# microusb_li_ion_charger.net
KiCad netlist of a schematic drawn in EAGLE
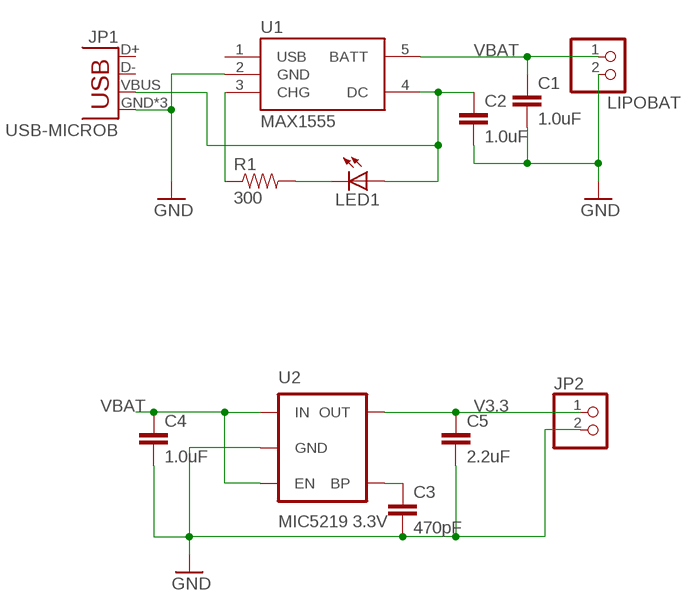
[diagram p0: schematic, sheet 1]

(export (version "E")
  (design (tool "Eeschema 10.0.6"))
  (components
    (comp (ref "C1")
      (value "1.0uF")
      (footprint "eagle-import:0805")
      (libsource (lib "eagle-import") (part "1.0UF-25V-+80/-20(0805)"))
    )
    (comp (ref "C2")
      (value "1.0uF")
      (footprint "eagle-import:0805")
      (libsource (lib "eagle-import") (part "1.0UF-25V-+80/-20(0805)"))
    )
    (comp (ref "C3")
      (value "470pF")
      (footprint "eagle-import:0805")
      (libsource (lib "eagle-import") (part "1.0UF-25V-+80/-20(0805)"))
    )
    (comp (ref "C4")
      (value "1.0uF")
      (footprint "eagle-import:0805")
      (libsource (lib "eagle-import") (part "1.0UF-25V-+80/-20(0805)"))
    )
    (comp (ref "C5")
      (value "2.2uF")
      (footprint "eagle-import:0805")
      (libsource (lib "eagle-import") (part "1.0UF-25V-+80/-20(0805)"))
    )
    (comp (ref "JP1")
      (value "USB-MICROB")
      (footprint "eagle-import:USB-MICROB")
      (libsource (lib "eagle-import") (part "USB-MICROB"))
    )
    (comp (ref "JP2")
      (value "PINHD-1X2")
      (footprint "eagle-import:1X02")
      (libsource (lib "eagle-import") (part "PINHD-1X2"))
    )
    (comp (ref "LED1")
      (value "LEDCHIP-LED0805")
      (footprint "eagle-import:CHIP-LED0805")
      (libsource (lib "eagle-import") (part "LEDCHIP-LED0805"))
    )
    (comp (ref "LIPOBAT")
      (value "JST_2PIN-SMT")
      (footprint "eagle-import:JST-PH-2-SMT")
      (libsource (lib "eagle-import") (part "JST_2PIN-SMT"))
    )
    (comp (ref "R1")
      (value "300")
      (footprint "eagle-import:0805")
      (libsource (lib "eagle-import") (part "RESISTOR0805-RES"))
    )
    (comp (ref "U1")
      (value "MAX1555")
      (footprint "eagle-import:SOT23-5")
      (libsource (lib "eagle-import") (part "MAX1555"))
    )
    (comp (ref "U2")
      (value "MIC5219 3.3V")
      (footprint "eagle-import:SOT23-5")
      (libsource (lib "eagle-import") (part "V_REG_MIC52193.3V"))
    )
  )
  (nets
    (net (code "1") (name "/V3.3") (class "Default")
      (node (ref "C5") (pin "1") (pinfunction "1_1") (pintype "passive"))
      (node (ref "JP2") (pin "1") (pinfunction "1_1") (pintype "passive"))
      (node (ref "U2") (pin "5") (pinfunction "OUT_5") (pintype "passive"))
    )
    (net (code "2") (name "/VBAT") (class "Default")
      (node (ref "C1") (pin "1") (pinfunction "1_1") (pintype "passive"))
      (node (ref "C4") (pin "1") (pinfunction "1_1") (pintype "passive"))
      (node (ref "LIPOBAT") (pin "1") (pinfunction "2_1") (pintype "passive"))
      (node (ref "U1") (pin "5") (pinfunction "BATT_5") (pintype "bidirectional"))
      (node (ref "U2") (pin "1") (pinfunction "IN_1") (pintype "input"))
      (node (ref "U2") (pin "3") (pinfunction "EN_3") (pintype "input"))
    )
    (net (code "3") (name "GND") (class "Default")
      (node (ref "C1") (pin "2") (pinfunction "2_2") (pintype "passive"))
      (node (ref "C2") (pin "2") (pinfunction "2_2") (pintype "passive"))
      (node (ref "C3") (pin "2") (pinfunction "2_2") (pintype "passive"))
      (node (ref "C4") (pin "2") (pinfunction "2_2") (pintype "passive"))
      (node (ref "C5") (pin "2") (pinfunction "2_2") (pintype "passive"))
      (node (ref "JP1") (pin "GND") (pinfunction "GND_GND") (pintype "bidirectional"))
      (node (ref "JP1") (pin "MT1") (pinfunction "GND_MT1") (pintype "bidirectional"))
      (node (ref "JP1") (pin "MT2") (pinfunction "GND_MT2") (pintype "bidirectional"))
      (node (ref "JP2") (pin "2") (pinfunction "2_2") (pintype "passive"))
      (node (ref "LIPOBAT") (pin "2") (pinfunction "1_2") (pintype "passive"))
      (node (ref "U1") (pin "2") (pinfunction "GND_2") (pintype "bidirectional"))
      (node (ref "U2") (pin "2") (pinfunction "GND_2") (pintype "input"))
    )
    (net (code "4") (name "Net-(LED1-PadC)") (class "Default")
      (node (ref "LED1") (pin "C") (pinfunction "C_C") (pintype "passive"))
      (node (ref "R1") (pin "2") (pinfunction "2_2") (pintype "passive"))
    )
    (net (code "5") (name "Net-(U1-CHG)") (class "Default")
      (node (ref "R1") (pin "1") (pinfunction "1_1") (pintype "passive"))
      (node (ref "U1") (pin "3") (pinfunction "CHG_3") (pintype "bidirectional"))
    )
    (net (code "6") (name "Net-(U1-DC)") (class "Default")
      (node (ref "C2") (pin "1") (pinfunction "1_1") (pintype "passive"))
      (node (ref "JP1") (pin "VBUS") (pinfunction "VBUS_VBUS") (pintype "bidirectional"))
      (node (ref "LED1") (pin "A") (pinfunction "A_A") (pintype "passive"))
      (node (ref "U1") (pin "4") (pinfunction "DC_4") (pintype "bidirectional"))
    )
    (net (code "7") (name "Net-(U2-BP)") (class "Default")
      (node (ref "C3") (pin "1") (pinfunction "1_1") (pintype "passive"))
      (node (ref "U2") (pin "4") (pinfunction "BP_4") (pintype "input"))
    )
    (net (code "8") (name "unconnected-(JP1-PadD+)") (class "Default")
      (node (ref "JP1") (pin "D+") (pinfunction "D+_D+") (pintype "bidirectional"))
    )
    (net (code "9") (name "unconnected-(JP1-PadD-)") (class "Default")
      (node (ref "JP1") (pin "D-") (pinfunction "D-_D-") (pintype "bidirectional"))
    )
    (net (code "10") (name "unconnected-(U1-USB-Pad1)") (class "Default")
      (node (ref "U1") (pin "1") (pinfunction "USB_1") (pintype "bidirectional"))
    )
  )
)
